# Meshtastic-MiniX-FakeTec.net
KiCad netlist of a schematic drawn in EasyEDA Pro
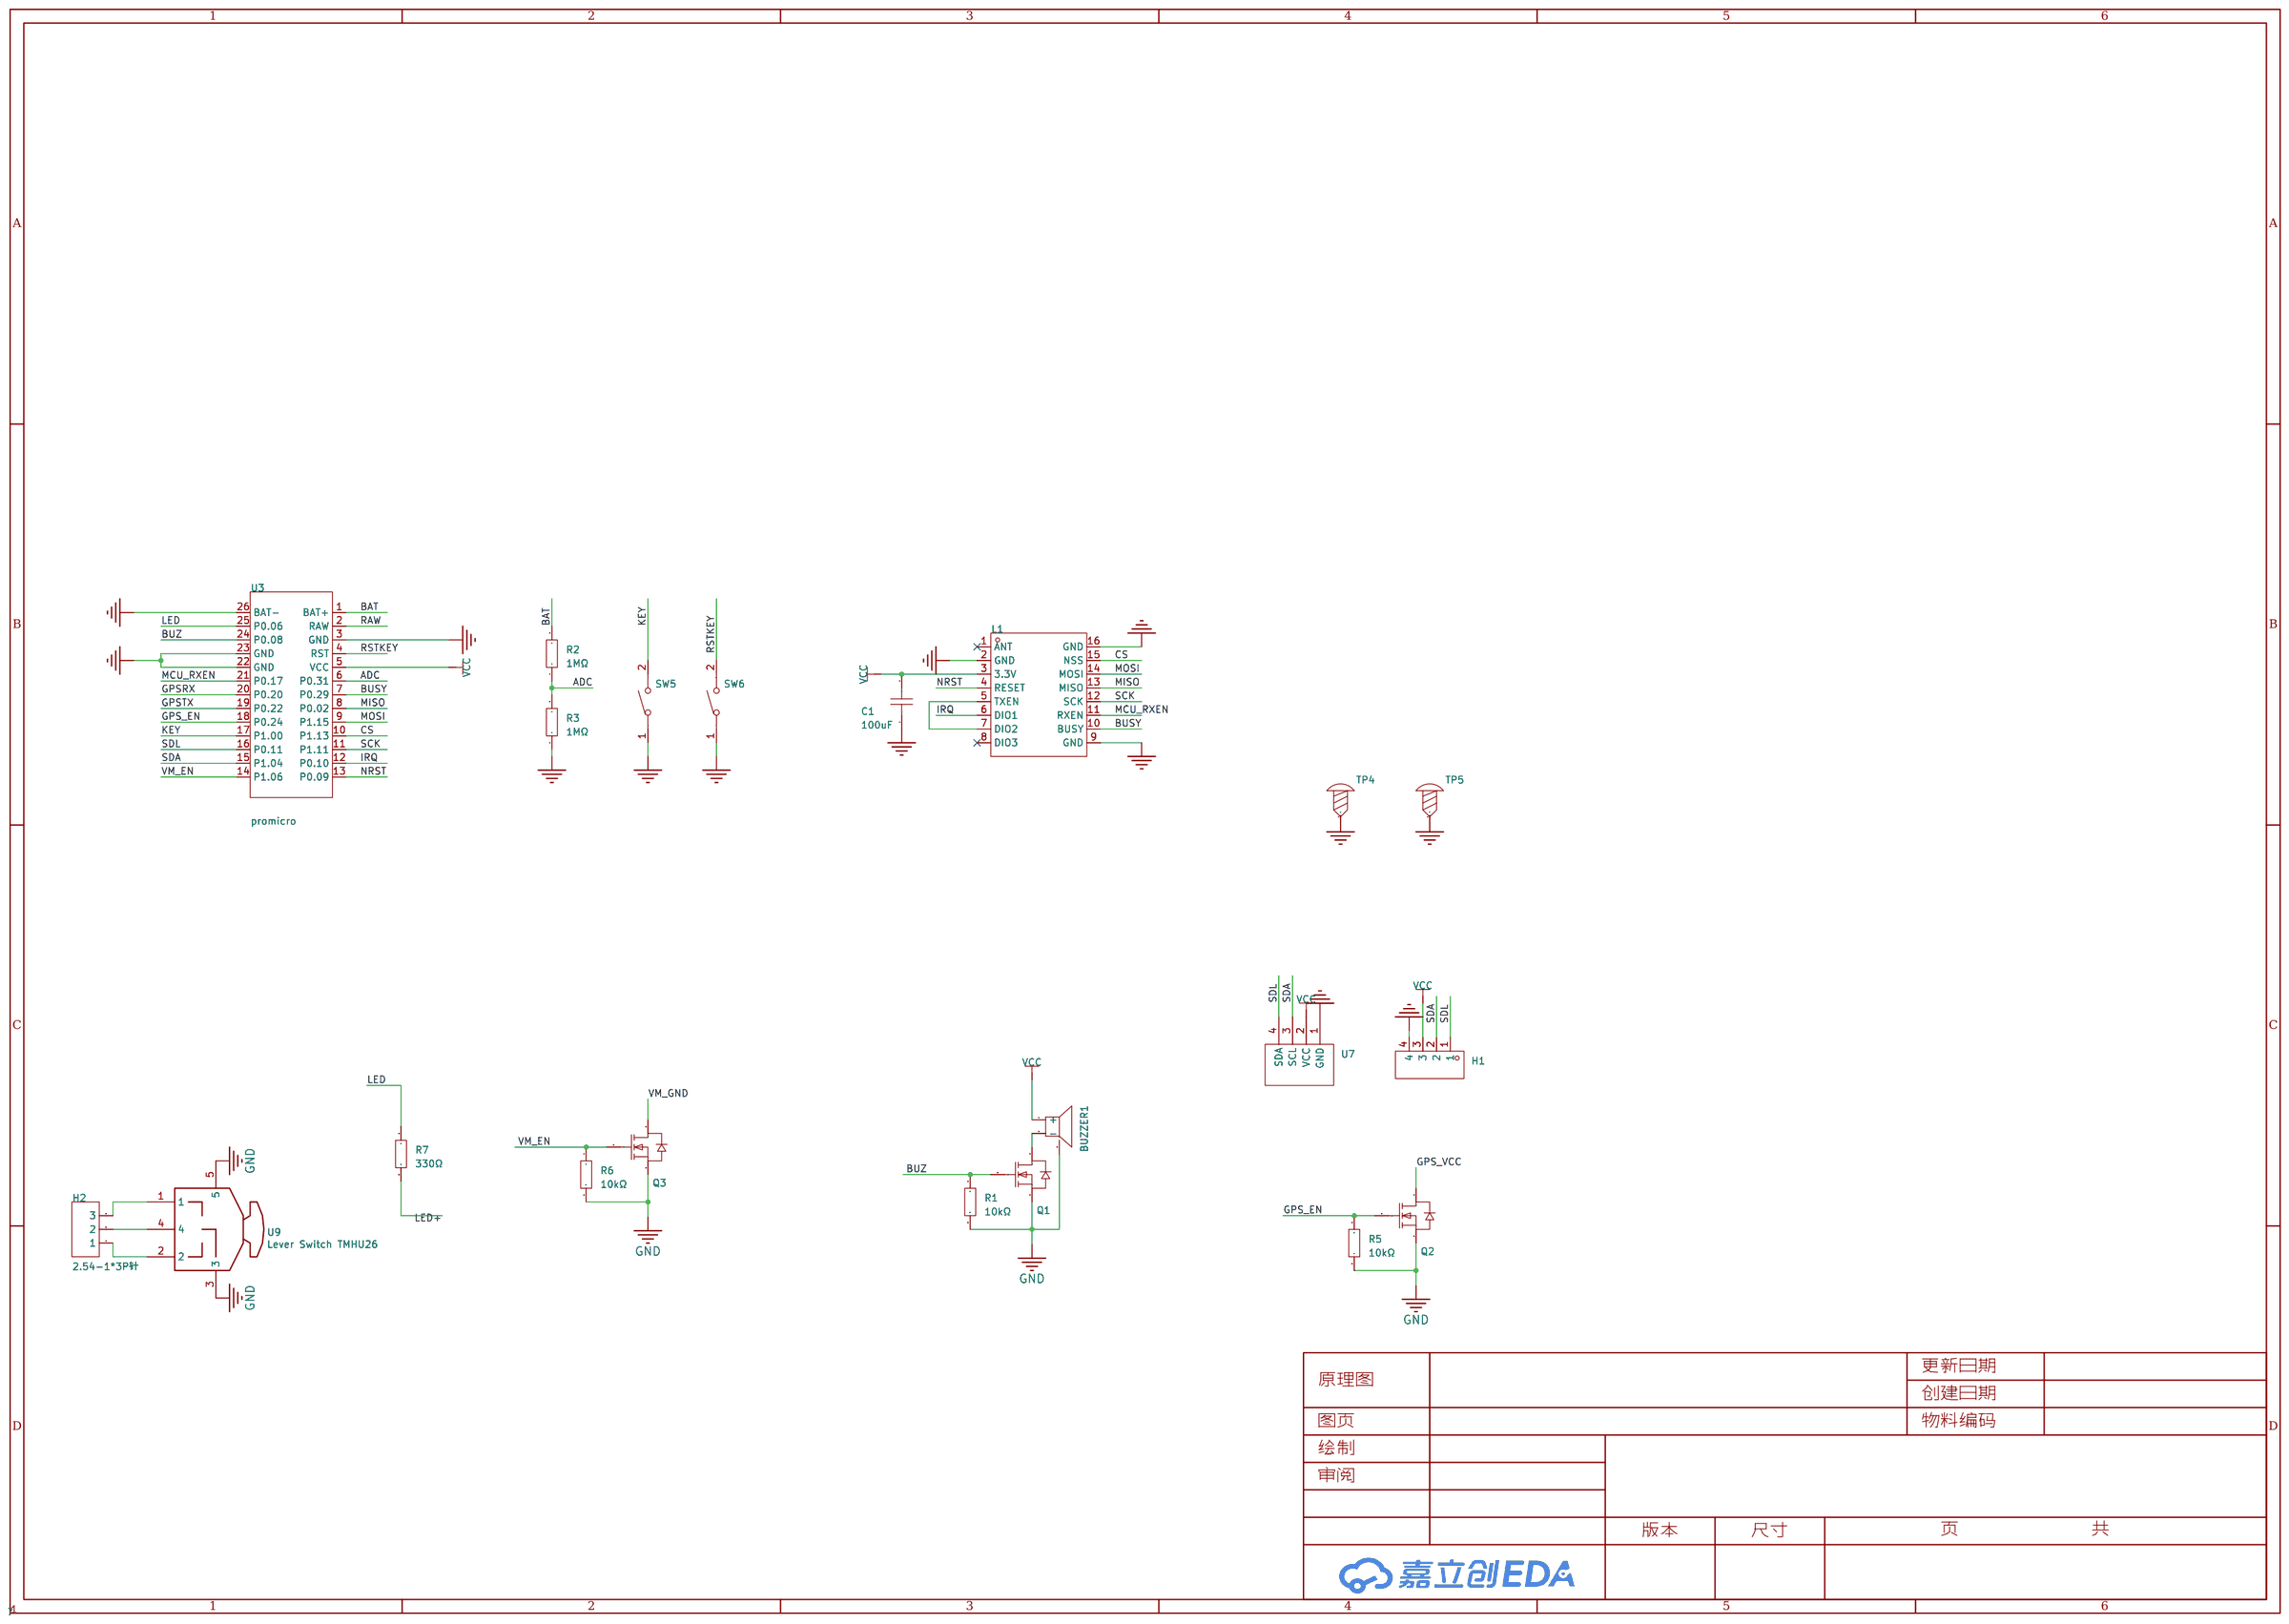
[diagram p0: schematic sheet]

(export (version "E")
  (design (tool "Eeschema 10.0.6"))
  (components
    (comp (ref "BUZZER1")
      (value "4kHz")
      (footprint "easyedapro:BUZ-SMD_L5.0-W5.5-P4.60")
      (description "驱动方式:无源(外部驱动);构造类型:电磁式;频率:4kHz;")
      (fields (field (name "Manufacturer Part") "MLT-5020") (field (name "Manufacturer") "华能"))
      (libsource (lib "easyedapro") (part "MLT-5020"))
    )
    (comp (ref "C1")
      (value "100uF")
      (footprint "easyedapro:C1206")
      (description "容值:100uF;精度:±20%;额定电压:10V;材质(温度系数):X5R;")
      (fields
        (field (name "Manufacturer Part") "HGC1206R5107M100NSPJ")
        (field (name "Manufacturer") "Chinocera(华瓷)")
      )
      (libsource (lib "easyedapro") (part "HGC1206R5107M100NSPJ"))
    )
    (comp (ref "H1")
      (value "PZ254V-11-04P")
      (footprint "easyedapro:HDR-TH_4P-P2.54-V-M")
      (fields (field (name "Manufacturer") "XFCN(兴飞)"))
      (libsource (lib "easyedapro") (part "PZ254V-11-04P_C2691448"))
    )
    (comp (ref "H2")
      (value "2.54-1*3P针")
      (footprint "easyedapro:HDR-TH_3P-P2.54-V-M-1")
      (fields (field (name "Manufacturer") "BOOMELE(博穆精密)"))
      (libsource (lib "easyedapro") (part "Header-Male-2.54_1x3"))
    )
    (comp (ref "L1")
      (value "Ra-01SH")
      (footprint "easyedapro:WIRELM-SMD_RA-01SH")
      (description "发射功率:22dBm;支持接口:SPI;接收灵敏度:-148dBm;")
      (fields (field (name "Manufacturer") "Ai-Thinker(安信可)"))
      (libsource (lib "easyedapro") (part "RA-01SH"))
    )
    (comp (ref "Q1")
      (value "AO3400A")
      (fields (field (name "Manufacturer") "AOS"))
      (libsource (lib "easyedapro") (part "AO3400A"))
    )
    (comp (ref "Q2")
      (value "AO3400A")
      (fields (field (name "Manufacturer") "AOS"))
      (libsource (lib "easyedapro") (part "AO3400A"))
    )
    (comp (ref "Q3")
      (value "AO3400A")
      (fields (field (name "Manufacturer") "AOS"))
      (libsource (lib "easyedapro") (part "AO3400A"))
    )
    (comp (ref "R1")
      (value "10kΩ")
      (footprint "easyedapro:R0603")
      (description "电阻类型:厚膜电阻;阻值:10kΩ;精度:±1%;功率:100mW;")
      (fields
        (field (name "Manufacturer Part") "0603WAF1002T5E")
        (field (name "Manufacturer") "UNI-ROYAL(厚声)")
      )
      (libsource (lib "easyedapro") (part "0603WAF1002T5E"))
    )
    (comp (ref "R2")
      (value "1MΩ")
      (footprint "easyedapro:R1206")
      (description "电阻类型:厚膜电阻;阻值:1MΩ;精度:±1%;功率:250mW;最大工作电压:200V;温度系数:±100ppm/°C;")
      (fields
        (field (name "Manufacturer Part") "1206W4F1004T5E")
        (field (name "Manufacturer") "UNI-ROYAL(厚声)")
      )
      (libsource (lib "easyedapro") (part "1206W4F1004T5E"))
    )
    (comp (ref "R3")
      (value "1MΩ")
      (footprint "easyedapro:R1206")
      (description "电阻类型:厚膜电阻;阻值:1MΩ;精度:±1%;功率:250mW;最大工作电压:200V;温度系数:±100ppm/°C;")
      (fields
        (field (name "Manufacturer Part") "1206W4F1004T5E")
        (field (name "Manufacturer") "UNI-ROYAL(厚声)")
      )
      (libsource (lib "easyedapro") (part "1206W4F1004T5E"))
    )
    (comp (ref "R5")
      (value "10kΩ")
      (footprint "easyedapro:R0603")
      (description "电阻类型:厚膜电阻;阻值:10kΩ;精度:±1%;功率:100mW;")
      (fields
        (field (name "Manufacturer Part") "0603WAF1002T5E")
        (field (name "Manufacturer") "UNI-ROYAL(厚声)")
      )
      (libsource (lib "easyedapro") (part "0603WAF1002T5E"))
    )
    (comp (ref "R6")
      (value "10kΩ")
      (footprint "easyedapro:R0603")
      (description "电阻类型:厚膜电阻;阻值:10kΩ;精度:±1%;功率:100mW;")
      (fields
        (field (name "Manufacturer Part") "0603WAF1002T5E")
        (field (name "Manufacturer") "UNI-ROYAL(厚声)")
      )
      (libsource (lib "easyedapro") (part "0603WAF1002T5E"))
    )
    (comp (ref "R7")
      (value "330Ω")
      (footprint "easyedapro:R0603")
      (fields
        (field (name "Manufacturer Part") "0603WAF3300T5E")
        (field (name "Manufacturer") "UNI-ROYAL(厚声)")
      )
      (libsource (lib "easyedapro") (part "0603WAF1002T5E"))
    )
    (comp (ref "SW5")
      (value "TS-1088-AR02016")
      (footprint "easyedapro:SW-SMD_L3.9-W3.0-P4.45")
      (fields (field (name "Manufacturer") "XUNPU(讯普)"))
      (libsource (lib "easyedapro") (part "TS-1088-AR02016"))
    )
    (comp (ref "SW6")
      (value "TS-1088-AR02016")
      (footprint "easyedapro:SW-SMD_L3.9-W3.0-P4.45")
      (fields (field (name "Manufacturer") "XUNPU(讯普)"))
      (libsource (lib "easyedapro") (part "TS-1088-AR02016"))
    )
    (comp (ref "TP4")
      (value "~")
      (footprint "easyedapro:M1.2螺丝")
      (libsource (lib "easyedapro") (part "M1.2螺丝"))
    )
    (comp (ref "TP5")
      (value "~")
      (footprint "easyedapro:M1.2螺丝")
      (libsource (lib "easyedapro") (part "M1.2螺丝"))
    )
    (comp (ref "U3")
      (value "promicro")
      (footprint "easyedapro:nrf_promicro")
      (libsource (lib "easyedapro") (part "nrf52840_promicro"))
    )
    (comp (ref "U7")
      (value "~")
      (footprint "easyedapro:SSD1306")
      (libsource (lib "easyedapro") (part "SSD1306"))
    )
    (comp (ref "U9")
      (value "Lever Switch TMHU26")
      (footprint "easyedapro:LEVEL SWITCH TMHU26")
      (fields (field (name "Contributor") "cedric.stoquer"))
      (libsource (lib "easyedapro") (part "Lever Switch TMHU26"))
    )
  )
  (nets
    (net (code "1") (name "/ADC") (class "Default")
      (node (ref "R2") (pin "1") (pinfunction "1_1") (pintype "input"))
      (node (ref "R3") (pin "2") (pinfunction "2_2") (pintype "input"))
      (node (ref "U3") (pin "6") (pinfunction "P0.31_6") (pintype "input"))
    )
    (net (code "2") (name "/BAT") (class "Default")
      (node (ref "R2") (pin "2") (pinfunction "2_2") (pintype "input"))
      (node (ref "U3") (pin "1") (pinfunction "BAT+_1") (pintype "input"))
    )
    (net (code "3") (name "/BUSY") (class "Default")
      (node (ref "L1") (pin "10") (pinfunction "BUSY_10") (pintype "unspecified"))
      (node (ref "U3") (pin "7") (pinfunction "P0.29_7") (pintype "input"))
    )
    (net (code "4") (name "/BUZ") (class "Default")
      (node (ref "Q1") (pin "1") (pinfunction "G_1") (pintype "input"))
      (node (ref "R1") (pin "1") (pinfunction "1_1") (pintype "input"))
      (node (ref "U3") (pin "24") (pinfunction "P0.08_24") (pintype "input"))
    )
    (net (code "5") (name "/CS") (class "Default")
      (node (ref "L1") (pin "15") (pinfunction "NSS_15") (pintype "unspecified"))
      (node (ref "U3") (pin "10") (pinfunction "P1.13_10") (pintype "input"))
    )
    (net (code "6") (name "/GPSRX") (class "Default")
      (node (ref "U3") (pin "20") (pinfunction "P0.20_20") (pintype "input"))
    )
    (net (code "7") (name "/GPSTX") (class "Default")
      (node (ref "U3") (pin "19") (pinfunction "P0.22_19") (pintype "input"))
    )
    (net (code "8") (name "/GPS_EN") (class "Default")
      (node (ref "Q2") (pin "1") (pinfunction "G_1") (pintype "input"))
      (node (ref "R5") (pin "1") (pinfunction "1_1") (pintype "input"))
      (node (ref "U3") (pin "18") (pinfunction "P0.24_18") (pintype "input"))
    )
    (net (code "9") (name "/GPS_VCC") (class "Default")
      (node (ref "Q2") (pin "3") (pinfunction "D_3") (pintype "input"))
    )
    (net (code "10") (name "/IRQ") (class "Default")
      (node (ref "L1") (pin "6") (pinfunction "DIO1_6") (pintype "unspecified"))
      (node (ref "U3") (pin "12") (pinfunction "P0.10_12") (pintype "input"))
    )
    (net (code "11") (name "/KEY") (class "Default")
      (node (ref "SW5") (pin "2") (pinfunction "2_2") (pintype "unspecified"))
      (node (ref "U3") (pin "17") (pinfunction "P1.00_17") (pintype "input"))
    )
    (net (code "12") (name "/LED") (class "Default")
      (node (ref "R7") (pin "1") (pinfunction "1_1") (pintype "input"))
      (node (ref "U3") (pin "25") (pinfunction "P0.06_25") (pintype "input"))
    )
    (net (code "13") (name "/LED+") (class "Default")
      (node (ref "R7") (pin "2") (pinfunction "2_2") (pintype "input"))
    )
    (net (code "14") (name "/MCU_RXEN") (class "Default")
      (node (ref "L1") (pin "11") (pinfunction "RXEN_11") (pintype "unspecified"))
      (node (ref "U3") (pin "21") (pinfunction "P0.17_21") (pintype "input"))
    )
    (net (code "15") (name "/MISO") (class "Default")
      (node (ref "L1") (pin "13") (pinfunction "MISO_13") (pintype "unspecified"))
      (node (ref "U3") (pin "8") (pinfunction "P0.02_8") (pintype "input"))
    )
    (net (code "16") (name "/MOSI") (class "Default")
      (node (ref "L1") (pin "14") (pinfunction "MOSI_14") (pintype "unspecified"))
      (node (ref "U3") (pin "9") (pinfunction "P1.15_9") (pintype "input"))
    )
    (net (code "17") (name "/NRST") (class "Default")
      (node (ref "L1") (pin "4") (pinfunction "RESET_4") (pintype "unspecified"))
      (node (ref "U3") (pin "13") (pinfunction "P0.09_13") (pintype "input"))
    )
    (net (code "18") (name "/RAW") (class "Default")
      (node (ref "U3") (pin "2") (pinfunction "RAW_2") (pintype "input"))
    )
    (net (code "19") (name "/RSTKEY") (class "Default")
      (node (ref "SW6") (pin "2") (pinfunction "2_2") (pintype "unspecified"))
      (node (ref "U3") (pin "4") (pinfunction "RST_4") (pintype "input"))
    )
    (net (code "20") (name "/SCK") (class "Default")
      (node (ref "L1") (pin "12") (pinfunction "SCK_12") (pintype "unspecified"))
      (node (ref "U3") (pin "11") (pinfunction "P1.11_11") (pintype "input"))
    )
    (net (code "21") (name "/SDA") (class "Default")
      (node (ref "H1") (pin "2") (pinfunction "2_2") (pintype "unspecified"))
      (node (ref "U3") (pin "15") (pinfunction "P1.04_15") (pintype "input"))
      (node (ref "U7") (pin "3") (pinfunction "SCL_3") (pintype "input"))
    )
    (net (code "22") (name "/SDL") (class "Default")
      (node (ref "H1") (pin "1") (pinfunction "1_1") (pintype "unspecified"))
      (node (ref "U3") (pin "16") (pinfunction "P0.11_16") (pintype "input"))
      (node (ref "U7") (pin "4") (pinfunction "SDA_4") (pintype "input"))
    )
    (net (code "23") (name "/VM_EN") (class "Default")
      (node (ref "Q3") (pin "1") (pinfunction "G_1") (pintype "input"))
      (node (ref "R6") (pin "1") (pinfunction "1_1") (pintype "input"))
      (node (ref "U3") (pin "14") (pinfunction "P1.06_14") (pintype "input"))
    )
    (net (code "24") (name "/VM_GND") (class "Default")
      (node (ref "Q3") (pin "3") (pinfunction "D_3") (pintype "input"))
    )
    (net (code "25") (name "GND") (class "Default")
      (node (ref "BUZZER1") (pin "3") (pinfunction "NC_3") (pintype "input"))
      (node (ref "C1") (pin "1") (pinfunction "1_1") (pintype "unspecified"))
      (node (ref "H1") (pin "4") (pinfunction "4_4") (pintype "unspecified"))
      (node (ref "L1") (pin "16") (pinfunction "GND_16") (pintype "unspecified"))
      (node (ref "L1") (pin "2") (pinfunction "GND_2") (pintype "unspecified"))
      (node (ref "L1") (pin "9") (pinfunction "GND_9") (pintype "unspecified"))
      (node (ref "Q1") (pin "2") (pinfunction "S_2") (pintype "input"))
      (node (ref "Q2") (pin "2") (pinfunction "S_2") (pintype "input"))
      (node (ref "Q3") (pin "2") (pinfunction "S_2") (pintype "input"))
      (node (ref "R1") (pin "2") (pinfunction "2_2") (pintype "input"))
      (node (ref "R3") (pin "1") (pinfunction "1_1") (pintype "input"))
      (node (ref "R5") (pin "2") (pinfunction "2_2") (pintype "input"))
      (node (ref "R6") (pin "2") (pinfunction "2_2") (pintype "input"))
      (node (ref "SW5") (pin "1") (pinfunction "1_1") (pintype "unspecified"))
      (node (ref "SW6") (pin "1") (pinfunction "1_1") (pintype "unspecified"))
      (node (ref "TP4") (pin "1") (pinfunction "1_1") (pintype "input"))
      (node (ref "TP5") (pin "1") (pinfunction "1_1") (pintype "input"))
      (node (ref "U3") (pin "22") (pinfunction "GND_22") (pintype "input"))
      (node (ref "U3") (pin "23") (pinfunction "GND_23") (pintype "input"))
      (node (ref "U3") (pin "26") (pinfunction "BAT-_26") (pintype "input"))
      (node (ref "U3") (pin "3") (pinfunction "GND_3") (pintype "input"))
      (node (ref "U7") (pin "1") (pinfunction "GND_1") (pintype "input"))
      (node (ref "U9") (pin "3") (pinfunction "3_3") (pintype "unspecified"))
      (node (ref "U9") (pin "5") (pinfunction "5_5") (pintype "unspecified"))
    )
    (net (code "26") (name "Net-(BUZZER1--)") (class "Default")
      (node (ref "BUZZER1") (pin "2") (pinfunction "-_2") (pintype "input"))
      (node (ref "Q1") (pin "3") (pinfunction "D_3") (pintype "input"))
    )
    (net (code "27") (name "Net-(H2-Pad1)") (class "Default")
      (node (ref "H2") (pin "1") (pinfunction "1_1") (pintype "input"))
      (node (ref "U9") (pin "2") (pinfunction "2_2") (pintype "unspecified"))
    )
    (net (code "28") (name "Net-(H2-Pad2)") (class "Default")
      (node (ref "H2") (pin "2") (pinfunction "2_2") (pintype "input"))
      (node (ref "U9") (pin "4") (pinfunction "4_4") (pintype "unspecified"))
    )
    (net (code "29") (name "Net-(H2-Pad3)") (class "Default")
      (node (ref "H2") (pin "3") (pinfunction "3_3") (pintype "input"))
      (node (ref "U9") (pin "1") (pinfunction "1_1") (pintype "unspecified"))
    )
    (net (code "30") (name "Net-(L1-DIO2)") (class "Default")
      (node (ref "L1") (pin "5") (pinfunction "TXEN_5") (pintype "unspecified"))
      (node (ref "L1") (pin "7") (pinfunction "DIO2_7") (pintype "unspecified"))
    )
    (net (code "31") (name "VCC") (class "Default")
      (node (ref "BUZZER1") (pin "1") (pinfunction "+_1") (pintype "input"))
      (node (ref "C1") (pin "2") (pinfunction "2_2") (pintype "unspecified"))
      (node (ref "H1") (pin "3") (pinfunction "3_3") (pintype "unspecified"))
      (node (ref "L1") (pin "3") (pinfunction "3.3V_3") (pintype "unspecified"))
      (node (ref "U3") (pin "5") (pinfunction "VCC_5") (pintype "input"))
      (node (ref "U7") (pin "2") (pinfunction "VCC_2") (pintype "input"))
    )
    (net (code "32") (name "unconnected-(L1-ANT-Pad1)") (class "Default")
      (node (ref "L1") (pin "1") (pinfunction "ANT_1") (pintype "unspecified+no_connect"))
    )
    (net (code "33") (name "unconnected-(L1-DIO3-Pad8)") (class "Default")
      (node (ref "L1") (pin "8") (pinfunction "DIO3_8") (pintype "unspecified+no_connect"))
    )
  )
)
